# linesensor.net
KiCad netlist of a schematic drawn in EAGLE
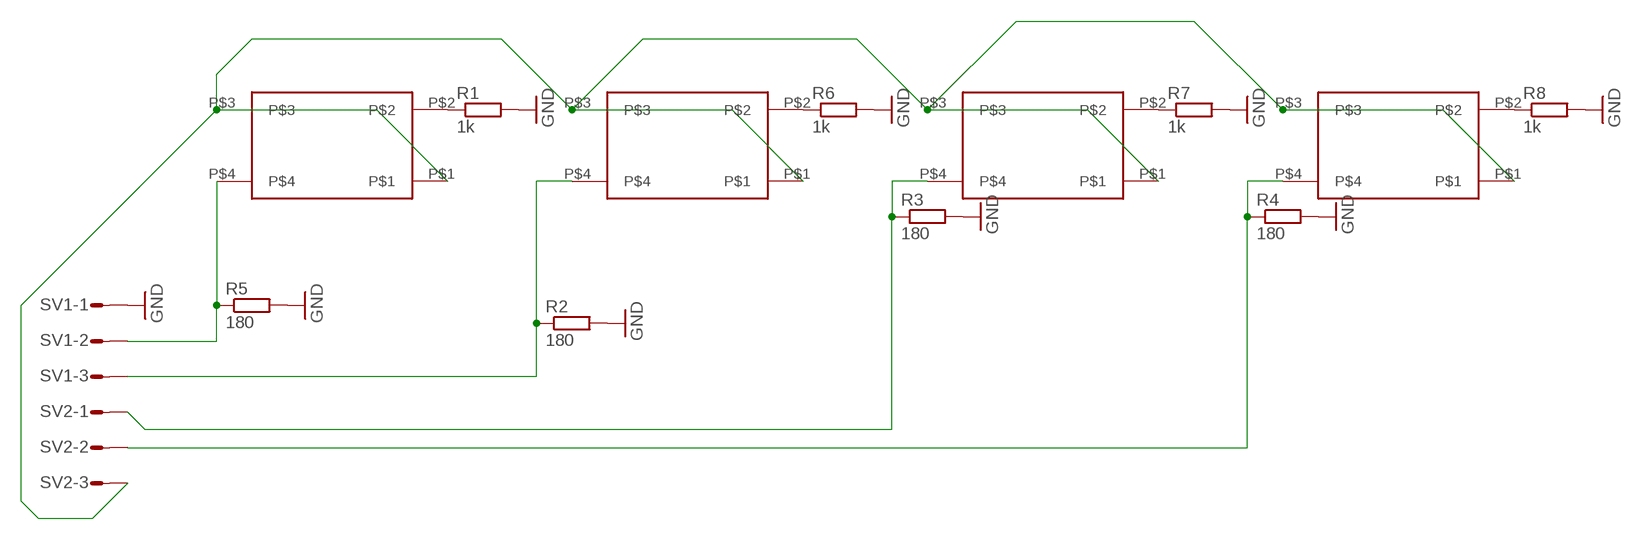
[diagram p0: schematic, sheet 1]

(export (version "E")
  (design (tool "Eeschema 10.0.6"))
  (components
    (comp (ref "R1")
      (value "1k")
      (footprint "eagle-import:0204V")
      (libsource (lib "eagle-import") (part "R-EU_0204/2V"))
    )
    (comp (ref "R2")
      (value "180")
      (footprint "eagle-import:0204V")
      (libsource (lib "eagle-import") (part "R-EU_0204/2V"))
    )
    (comp (ref "R3")
      (value "180")
      (footprint "eagle-import:0204V")
      (libsource (lib "eagle-import") (part "R-EU_0204/2V"))
    )
    (comp (ref "R4")
      (value "180")
      (footprint "eagle-import:0204V")
      (libsource (lib "eagle-import") (part "R-EU_0204/2V"))
    )
    (comp (ref "R5")
      (value "180")
      (footprint "eagle-import:0204V")
      (libsource (lib "eagle-import") (part "R-EU_0204/2V"))
    )
    (comp (ref "R6")
      (value "1k")
      (footprint "eagle-import:0204V")
      (libsource (lib "eagle-import") (part "R-EU_0204/2V"))
    )
    (comp (ref "R7")
      (value "1k")
      (footprint "eagle-import:0204V")
      (libsource (lib "eagle-import") (part "R-EU_0204/2V"))
    )
    (comp (ref "R8")
      (value "1k")
      (footprint "eagle-import:0204V")
      (libsource (lib "eagle-import") (part "R-EU_0204/2V"))
    )
    (comp (ref "SV1")
      (value "S03P")
      (footprint "eagle-import:S03P")
      (libsource (lib "eagle-import") (part "S03P"))
    )
    (comp (ref "SV2")
      (value "S03P")
      (footprint "eagle-import:S03P")
      (libsource (lib "eagle-import") (part "S03P"))
    )
    (comp (ref "U$1")
      (value "TPR105F")
      (footprint "eagle-import:TPR105F")
      (libsource (lib "eagle-import") (part "TPR105F"))
    )
    (comp (ref "U$2")
      (value "TPR105F")
      (footprint "eagle-import:TPR105F")
      (libsource (lib "eagle-import") (part "TPR105F"))
    )
    (comp (ref "U$3")
      (value "TPR105F")
      (footprint "eagle-import:TPR105F")
      (libsource (lib "eagle-import") (part "TPR105F"))
    )
    (comp (ref "U$4")
      (value "TPR105F")
      (footprint "eagle-import:TPR105F")
      (libsource (lib "eagle-import") (part "TPR105F"))
    )
  )
  (nets
    (net (code "1") (name "GND") (class "Default")
      (node (ref "R1") (pin "2") (pinfunction "2_2") (pintype "passive"))
      (node (ref "R2") (pin "2") (pinfunction "2_2") (pintype "passive"))
      (node (ref "R3") (pin "2") (pinfunction "2_2") (pintype "passive"))
      (node (ref "R4") (pin "2") (pinfunction "2_2") (pintype "passive"))
      (node (ref "R5") (pin "2") (pinfunction "2_2") (pintype "passive"))
      (node (ref "R6") (pin "2") (pinfunction "2_2") (pintype "passive"))
      (node (ref "R7") (pin "2") (pinfunction "2_2") (pintype "passive"))
      (node (ref "R8") (pin "2") (pinfunction "2_2") (pintype "passive"))
      (node (ref "SV1") (pin "1") (pinfunction "S_1") (pintype "passive"))
    )
    (net (code "2") (name "Net-(R1-Pad1)") (class "Default")
      (node (ref "R1") (pin "1") (pinfunction "1_1") (pintype "passive"))
      (node (ref "U$1") (pin "P$2") (pinfunction "P$2_P$2") (pintype "bidirectional"))
    )
    (net (code "3") (name "Net-(R6-Pad1)") (class "Default")
      (node (ref "R6") (pin "1") (pinfunction "1_1") (pintype "passive"))
      (node (ref "U$2") (pin "P$2") (pinfunction "P$2_P$2") (pintype "bidirectional"))
    )
    (net (code "4") (name "Net-(R7-Pad1)") (class "Default")
      (node (ref "R7") (pin "1") (pinfunction "1_1") (pintype "passive"))
      (node (ref "U$3") (pin "P$2") (pinfunction "P$2_P$2") (pintype "bidirectional"))
    )
    (net (code "5") (name "Net-(R8-Pad1)") (class "Default")
      (node (ref "R8") (pin "1") (pinfunction "1_1") (pintype "passive"))
      (node (ref "U$4") (pin "P$2") (pinfunction "P$2_P$2") (pintype "bidirectional"))
    )
    (net (code "6") (name "Net-(SV1B-S)") (class "Default")
      (node (ref "R5") (pin "1") (pinfunction "1_1") (pintype "passive"))
      (node (ref "SV1") (pin "2") (pinfunction "S_2") (pintype "passive"))
      (node (ref "U$1") (pin "P$4") (pinfunction "P$4_P$4") (pintype "bidirectional"))
    )
    (net (code "7") (name "Net-(SV1C-S)") (class "Default")
      (node (ref "R2") (pin "1") (pinfunction "1_1") (pintype "passive"))
      (node (ref "SV1") (pin "3") (pinfunction "S_3") (pintype "passive"))
      (node (ref "U$2") (pin "P$4") (pinfunction "P$4_P$4") (pintype "bidirectional"))
    )
    (net (code "8") (name "Net-(SV2A-S)") (class "Default")
      (node (ref "R3") (pin "1") (pinfunction "1_1") (pintype "passive"))
      (node (ref "SV2") (pin "1") (pinfunction "S_1") (pintype "passive"))
      (node (ref "U$3") (pin "P$4") (pinfunction "P$4_P$4") (pintype "bidirectional"))
    )
    (net (code "9") (name "Net-(SV2B-S)") (class "Default")
      (node (ref "R4") (pin "1") (pinfunction "1_1") (pintype "passive"))
      (node (ref "SV2") (pin "2") (pinfunction "S_2") (pintype "passive"))
      (node (ref "U$4") (pin "P$4") (pinfunction "P$4_P$4") (pintype "bidirectional"))
    )
    (net (code "10") (name "Net-(SV2C-S)") (class "Default")
      (node (ref "SV2") (pin "3") (pinfunction "S_3") (pintype "passive"))
      (node (ref "U$1") (pin "P$1") (pinfunction "P$1_P$1") (pintype "bidirectional"))
      (node (ref "U$1") (pin "P$3") (pinfunction "P$3_P$3") (pintype "bidirectional"))
      (node (ref "U$2") (pin "P$1") (pinfunction "P$1_P$1") (pintype "bidirectional"))
      (node (ref "U$2") (pin "P$3") (pinfunction "P$3_P$3") (pintype "bidirectional"))
      (node (ref "U$3") (pin "P$1") (pinfunction "P$1_P$1") (pintype "bidirectional"))
      (node (ref "U$3") (pin "P$3") (pinfunction "P$3_P$3") (pintype "bidirectional"))
      (node (ref "U$4") (pin "P$1") (pinfunction "P$1_P$1") (pintype "bidirectional"))
      (node (ref "U$4") (pin "P$3") (pinfunction "P$3_P$3") (pintype "bidirectional"))
    )
  )
)
